# GardenSense_RevB.net
KiCad netlist of a schematic drawn in Altium Designer
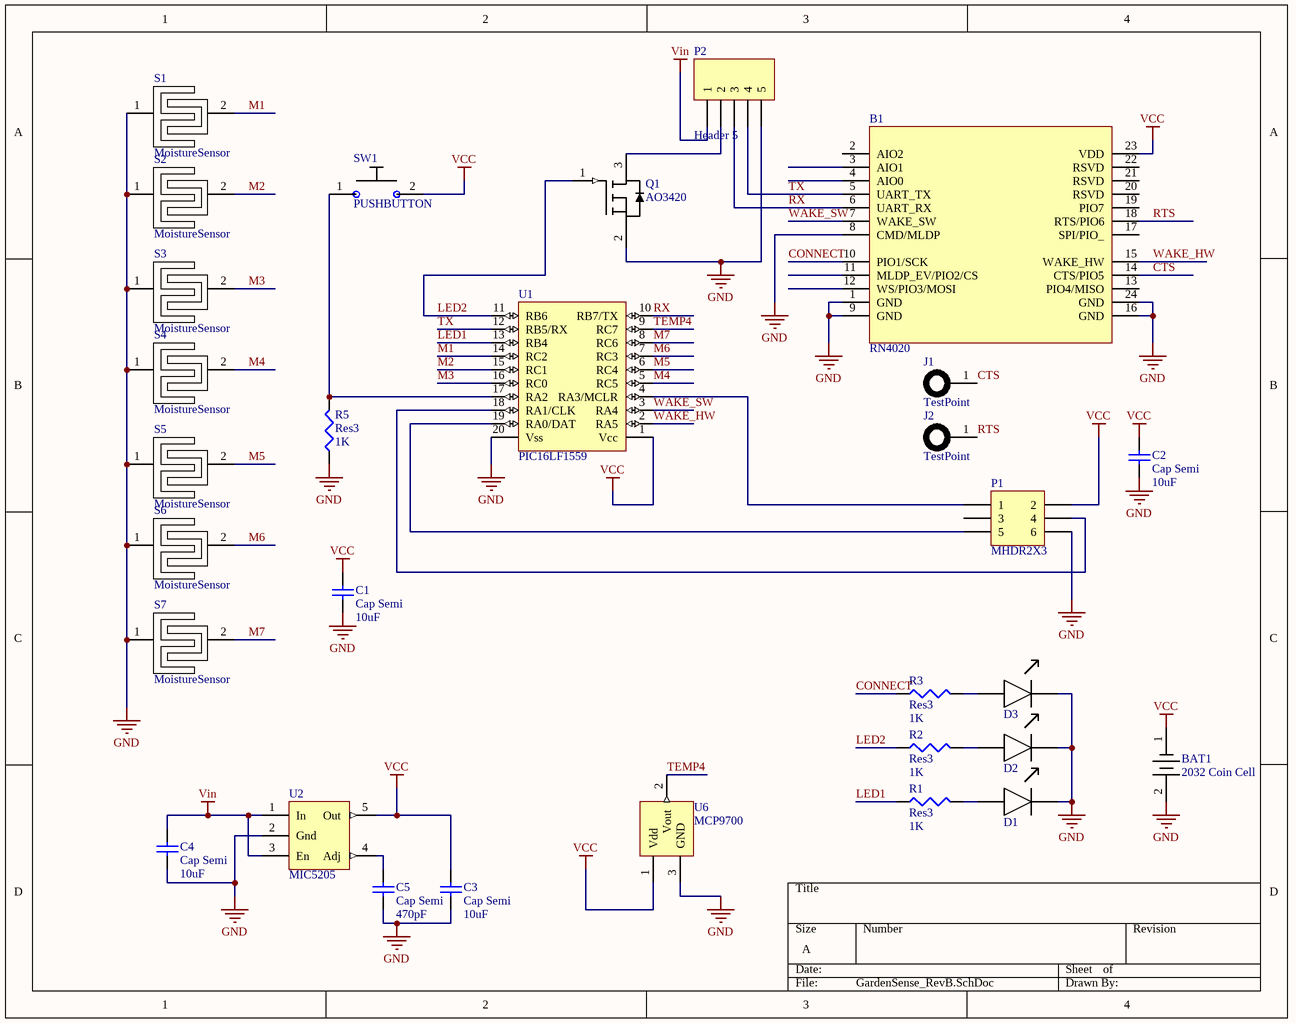
[diagram p0: GardenSense_RevB.SchDoc]

(export (version "E")
  (design (tool "Eeschema 10.0.6"))
  (components
    (comp (ref "B1") (value "RN4020") (footprint "RN4020 MODULE-24") (libsource (lib "Phil") (part "RN4020")))
    (comp (ref "BAT1")
      (value "2032 Coin Cell")
      (footprint "Keystone_3002_2032_CoinCell")
      (libsource (lib "Phil") (part "2032 Coin Cell"))
    )
    (comp (ref "C1")
      (value "Cap Semi")
      (footprint "1608[0603]")
      (description "Capacitor (Semiconductor SIM Model)")
      (fields (field (name "ALTIUM_VALUE") "10uF") (field (name "PUBLISHER") "Altium Limited"))
      (libsource (lib "Miscellaneous Devices") (part "Cap Semi"))
    )
    (comp (ref "C2")
      (value "Cap Semi")
      (footprint "1608[0603]")
      (description "Capacitor (Semiconductor SIM Model)")
      (fields (field (name "ALTIUM_VALUE") "10uF") (field (name "PUBLISHER") "Altium Limited"))
      (libsource (lib "Miscellaneous Devices") (part "Cap Semi"))
    )
    (comp (ref "C3")
      (value "Cap Semi")
      (footprint "1608[0603]")
      (description "Capacitor (Semiconductor SIM Model)")
      (fields (field (name "ALTIUM_VALUE") "10uF") (field (name "PUBLISHER") "Altium Limited"))
      (libsource (lib "Miscellaneous Devices") (part "Cap Semi"))
    )
    (comp (ref "C4")
      (value "Cap Semi")
      (footprint "1608[0603]")
      (description "Capacitor (Semiconductor SIM Model)")
      (fields (field (name "ALTIUM_VALUE") "10uF") (field (name "PUBLISHER") "Altium Limited"))
      (libsource (lib "Miscellaneous Devices") (part "Cap Semi"))
    )
    (comp (ref "C5")
      (value "Cap Semi")
      (footprint "1608[0603]")
      (description "Capacitor (Semiconductor SIM Model)")
      (fields (field (name "ALTIUM_VALUE") "470pF") (field (name "PUBLISHER") "Altium Limited"))
      (libsource (lib "Miscellaneous Devices") (part "Cap Semi"))
    )
    (comp (ref "D1") (value "LED") (footprint "603_") (libsource (lib "Phil") (part "LED")))
    (comp (ref "D2") (value "LED") (footprint "603_") (libsource (lib "Phil") (part "LED")))
    (comp (ref "D3") (value "LED") (footprint "603_") (libsource (lib "Phil") (part "LED")))
    (comp (ref "J1") (value "TestPoint") (footprint "TestPoint") (libsource (lib "Phil") (part "TestPoint")))
    (comp (ref "J2") (value "TestPoint") (footprint "TestPoint") (libsource (lib "Phil") (part "TestPoint")))
    (comp (ref "P1")
      (value "MHDR2X3")
      (footprint "MHDR2X3")
      (description "Header, 3-Pin, Dual row")
      (fields (field (name "PUBLISHER") "Altium Limited"))
      (libsource (lib "Miscellaneous Connectors") (part "MHDR2X3"))
    )
    (comp (ref "P2")
      (value "Header 5")
      (footprint "HDR1X5")
      (description "Header, 5-Pin")
      (fields (field (name "PUBLISHER") "Altium Limited"))
      (libsource (lib "Miscellaneous Connectors") (part "Header 5"))
    )
    (comp (ref "Q1") (value "AO3420") (footprint "PcbLib1:SOT23_N") (libsource (lib "Phil") (part "AO3420")))
    (comp (ref "R1")
      (value "Res3")
      (footprint "J1-0603")
      (description "Resistor")
      (fields (field (name "ALTIUM_VALUE") "1K") (field (name "PUBLISHER") "Altium Limited"))
      (libsource (lib "Miscellaneous Devices") (part "Res3"))
    )
    (comp (ref "R2")
      (value "Res3")
      (footprint "J1-0603")
      (description "Resistor")
      (fields (field (name "ALTIUM_VALUE") "1K") (field (name "PUBLISHER") "Altium Limited"))
      (libsource (lib "Miscellaneous Devices") (part "Res3"))
    )
    (comp (ref "R3")
      (value "Res3")
      (footprint "J1-0603")
      (description "Resistor")
      (fields (field (name "ALTIUM_VALUE") "1K") (field (name "PUBLISHER") "Altium Limited"))
      (libsource (lib "Miscellaneous Devices") (part "Res3"))
    )
    (comp (ref "R5")
      (value "Res3")
      (footprint "J1-0603")
      (description "Resistor")
      (fields (field (name "ALTIUM_VALUE") "1K") (field (name "PUBLISHER") "Altium Limited"))
      (libsource (lib "Miscellaneous Devices") (part "Res3"))
    )
    (comp (ref "S1")
      (value "MoistureSensor")
      (footprint "MOISTURE_2")
      (libsource (lib "Phil") (part "MoistureSensor"))
    )
    (comp (ref "S2")
      (value "MoistureSensor")
      (footprint "MOISTURE_2")
      (libsource (lib "Phil") (part "MoistureSensor"))
    )
    (comp (ref "S3")
      (value "MoistureSensor")
      (footprint "Phil:MOISTURE_2")
      (libsource (lib "Phil") (part "MoistureSensor"))
    )
    (comp (ref "S4")
      (value "MoistureSensor")
      (footprint "MOISTURE_2")
      (libsource (lib "Phil") (part "MoistureSensor"))
    )
    (comp (ref "S5")
      (value "MoistureSensor")
      (footprint "MOISTURE_2")
      (libsource (lib "Phil") (part "MoistureSensor"))
    )
    (comp (ref "S6")
      (value "MoistureSensor")
      (footprint "MOISTURE_2")
      (libsource (lib "Phil") (part "MoistureSensor"))
    )
    (comp (ref "S7")
      (value "MoistureSensor")
      (footprint "MOISTURE_2")
      (libsource (lib "Phil") (part "MoistureSensor"))
    )
    (comp (ref "SW1")
      (value "PUSHBUTTON")
      (footprint "PUSHBUTTON")
      (description "TE 5-1437565-0")
      (libsource (lib "Phil") (part "PUSHBUTTON"))
    )
    (comp (ref "U1")
      (value "PIC16LF1559")
      (footprint "SSOP-20")
      (libsource (lib "Phil") (part "PIC16LF1559"))
    )
    (comp (ref "U2")
      (value "MIC5205")
      (footprint "PcbLib1:SOT23-5_N")
      (libsource (lib "Phil") (part "MIC5205"))
    )
    (comp (ref "U6")
      (value "MCP9700")
      (footprint "Miscellaneous Devices:SOT23_M")
      (libsource (lib "Phil") (part "MCP9700"))
    )
  )
  (nets
    (net (code "1") (name "/CONNECT") (class "Default")
      (node (ref "B1") (pin "10") (pinfunction "PIO1/SCK_10") (pintype "passive"))
      (node (ref "R3") (pin "1") (pinfunction "1_1") (pintype "passive"))
    )
    (net (code "2") (name "/CTS") (class "Default")
      (node (ref "B1") (pin "14") (pinfunction "CTS/PIO5_14") (pintype "passive"))
      (node (ref "J1") (pin "1") (pinfunction "1_1") (pintype "passive"))
    )
    (net (code "3") (name "/LED1") (class "Default")
      (node (ref "R1") (pin "1") (pinfunction "1_1") (pintype "passive"))
      (node (ref "U1") (pin "13") (pinfunction "RB4_13") (pintype "bidirectional"))
    )
    (net (code "4") (name "/LED2") (class "Default")
      (node (ref "Q1") (pin "1") (pinfunction "G_1") (pintype "input"))
      (node (ref "R2") (pin "1") (pinfunction "1_1") (pintype "passive"))
      (node (ref "U1") (pin "11") (pinfunction "RB6_11") (pintype "bidirectional"))
    )
    (net (code "5") (name "/M1") (class "Default")
      (node (ref "S1") (pin "2") (pinfunction "2_2") (pintype "passive"))
      (node (ref "U1") (pin "14") (pinfunction "RC2_14") (pintype "bidirectional"))
    )
    (net (code "6") (name "/M2") (class "Default")
      (node (ref "S2") (pin "2") (pinfunction "2_2") (pintype "passive"))
      (node (ref "U1") (pin "15") (pinfunction "RC1_15") (pintype "bidirectional"))
    )
    (net (code "7") (name "/M3") (class "Default")
      (node (ref "S3") (pin "2") (pinfunction "2_2") (pintype "passive"))
      (node (ref "U1") (pin "16") (pinfunction "RC0_16") (pintype "bidirectional"))
    )
    (net (code "8") (name "/M4") (class "Default")
      (node (ref "S4") (pin "2") (pinfunction "2_2") (pintype "passive"))
      (node (ref "U1") (pin "5") (pinfunction "RC5_5") (pintype "bidirectional"))
    )
    (net (code "9") (name "/M5") (class "Default")
      (node (ref "S5") (pin "2") (pinfunction "2_2") (pintype "passive"))
      (node (ref "U1") (pin "6") (pinfunction "RC4_6") (pintype "bidirectional"))
    )
    (net (code "10") (name "/M6") (class "Default")
      (node (ref "S6") (pin "2") (pinfunction "2_2") (pintype "passive"))
      (node (ref "U1") (pin "7") (pinfunction "RC3_7") (pintype "bidirectional"))
    )
    (net (code "11") (name "/M7") (class "Default")
      (node (ref "S7") (pin "2") (pinfunction "2_2") (pintype "passive"))
      (node (ref "U1") (pin "8") (pinfunction "RC6_8") (pintype "bidirectional"))
    )
    (net (code "12") (name "/RTS") (class "Default")
      (node (ref "B1") (pin "18") (pinfunction "RTS/PIO6_18") (pintype "passive"))
      (node (ref "J2") (pin "1") (pinfunction "1_1") (pintype "passive"))
    )
    (net (code "13") (name "/RX") (class "Default")
      (node (ref "B1") (pin "6") (pinfunction "UART_RX_6") (pintype "passive"))
      (node (ref "P2") (pin "3") (pinfunction "3_3") (pintype "passive"))
      (node (ref "U1") (pin "10") (pinfunction "RB7/TX_10") (pintype "bidirectional"))
    )
    (net (code "14") (name "/TEMP4") (class "Default")
      (node (ref "U1") (pin "9") (pinfunction "RC7_9") (pintype "bidirectional"))
      (node (ref "U6") (pin "2") (pinfunction "Vout_2") (pintype "output"))
    )
    (net (code "15") (name "/TX") (class "Default")
      (node (ref "B1") (pin "5") (pinfunction "UART_TX_5") (pintype "passive"))
      (node (ref "P2") (pin "4") (pinfunction "4_4") (pintype "passive"))
      (node (ref "U1") (pin "12") (pinfunction "RB5/RX_12") (pintype "bidirectional"))
    )
    (net (code "16") (name "/WAKE_HW") (class "Default")
      (node (ref "B1") (pin "15") (pinfunction "WAKE_HW_15") (pintype "passive"))
      (node (ref "U1") (pin "2") (pinfunction "RA5_2") (pintype "bidirectional"))
    )
    (net (code "17") (name "/WAKE_SW") (class "Default")
      (node (ref "B1") (pin "7") (pinfunction "WAKE_SW_7") (pintype "passive"))
      (node (ref "U1") (pin "3") (pinfunction "RA4_3") (pintype "bidirectional"))
    )
    (net (code "18") (name "GND") (class "Default")
      (node (ref "B1") (pin "1") (pinfunction "GND_1") (pintype "power_in"))
      (node (ref "B1") (pin "16") (pinfunction "GND_16") (pintype "power_in"))
      (node (ref "B1") (pin "24") (pinfunction "GND_24") (pintype "passive"))
      (node (ref "B1") (pin "8") (pinfunction "CMD/MLDP_8") (pintype "passive"))
      (node (ref "B1") (pin "9") (pinfunction "GND_9") (pintype "power_in"))
      (node (ref "BAT1") (pin "2") (pinfunction "2_2") (pintype "passive"))
      (node (ref "C1") (pin "1") (pinfunction "1_1") (pintype "passive"))
      (node (ref "C2") (pin "1") (pinfunction "1_1") (pintype "passive"))
      (node (ref "C3") (pin "1") (pinfunction "1_1") (pintype "passive"))
      (node (ref "C4") (pin "1") (pinfunction "1_1") (pintype "passive"))
      (node (ref "C5") (pin "1") (pinfunction "1_1") (pintype "passive"))
      (node (ref "D1") (pin "2") (pinfunction "2_2") (pintype "passive"))
      (node (ref "D2") (pin "2") (pinfunction "2_2") (pintype "passive"))
      (node (ref "D3") (pin "2") (pinfunction "2_2") (pintype "passive"))
      (node (ref "P1") (pin "6") (pinfunction "6_6") (pintype "passive"))
      (node (ref "P2") (pin "5") (pinfunction "5_5") (pintype "passive"))
      (node (ref "Q1") (pin "2") (pinfunction "S_2") (pintype "power_in"))
      (node (ref "R5") (pin "1") (pinfunction "1_1") (pintype "passive"))
      (node (ref "S1") (pin "1") (pinfunction "1_1") (pintype "passive"))
      (node (ref "S2") (pin "1") (pinfunction "1_1") (pintype "passive"))
      (node (ref "S3") (pin "1") (pinfunction "1_1") (pintype "passive"))
      (node (ref "S4") (pin "1") (pinfunction "1_1") (pintype "passive"))
      (node (ref "S5") (pin "1") (pinfunction "1_1") (pintype "passive"))
      (node (ref "S6") (pin "1") (pinfunction "1_1") (pintype "passive"))
      (node (ref "S7") (pin "1") (pinfunction "1_1") (pintype "passive"))
      (node (ref "U1") (pin "20") (pinfunction "Vss_20") (pintype "power_in"))
      (node (ref "U2") (pin "2") (pinfunction "Gnd_2") (pintype "power_in"))
      (node (ref "U6") (pin "3") (pinfunction "GND_3") (pintype "power_in"))
    )
    (net (code "19") (name "Net-(D1-Pad1)") (class "Default")
      (node (ref "D1") (pin "1") (pinfunction "1_1") (pintype "passive"))
      (node (ref "R1") (pin "2") (pinfunction "2_2") (pintype "passive"))
    )
    (net (code "20") (name "Net-(D2-Pad1)") (class "Default")
      (node (ref "D2") (pin "1") (pinfunction "1_1") (pintype "passive"))
      (node (ref "R2") (pin "2") (pinfunction "2_2") (pintype "passive"))
    )
    (net (code "21") (name "Net-(D3-Pad1)") (class "Default")
      (node (ref "D3") (pin "1") (pinfunction "1_1") (pintype "passive"))
      (node (ref "R3") (pin "2") (pinfunction "2_2") (pintype "passive"))
    )
    (net (code "22") (name "Net-(Q1-D)") (class "Default")
      (node (ref "P2") (pin "2") (pinfunction "2_2") (pintype "passive"))
      (node (ref "Q1") (pin "3") (pinfunction "D_3") (pintype "power_in"))
    )
    (net (code "23") (name "Net-(U1-RA0{slash}DAT)") (class "Default")
      (node (ref "P1") (pin "5") (pinfunction "5_5") (pintype "passive"))
      (node (ref "U1") (pin "19") (pinfunction "RA0/DAT_19") (pintype "bidirectional"))
    )
    (net (code "24") (name "Net-(U1-RA1{slash}CLK)") (class "Default")
      (node (ref "P1") (pin "4") (pinfunction "4_4") (pintype "passive"))
      (node (ref "U1") (pin "18") (pinfunction "RA1/CLK_18") (pintype "bidirectional"))
    )
    (net (code "25") (name "Net-(U1-RA2)") (class "Default")
      (node (ref "R5") (pin "2") (pinfunction "2_2") (pintype "passive"))
      (node (ref "SW1") (pin "1") (pinfunction "1_1") (pintype "passive"))
      (node (ref "U1") (pin "17") (pinfunction "RA2_17") (pintype "bidirectional"))
    )
    (net (code "26") (name "Net-(U1-RA3{slash}MCLR)") (class "Default")
      (node (ref "P1") (pin "1") (pinfunction "1_1") (pintype "passive"))
      (node (ref "U1") (pin "4") (pinfunction "RA3/MCLR_4") (pintype "bidirectional"))
    )
    (net (code "27") (name "Net-(U2-Adj)") (class "Default")
      (node (ref "C5") (pin "2") (pinfunction "2_2") (pintype "passive"))
      (node (ref "U2") (pin "4") (pinfunction "Adj_4") (pintype "output"))
    )
    (net (code "28") (name "VCC") (class "Default")
      (node (ref "B1") (pin "23") (pinfunction "VDD_23") (pintype "power_in"))
      (node (ref "BAT1") (pin "1") (pinfunction "1_1") (pintype "passive"))
      (node (ref "C1") (pin "2") (pinfunction "2_2") (pintype "passive"))
      (node (ref "C2") (pin "2") (pinfunction "2_2") (pintype "passive"))
      (node (ref "C3") (pin "2") (pinfunction "2_2") (pintype "passive"))
      (node (ref "P1") (pin "2") (pinfunction "2_2") (pintype "passive"))
      (node (ref "SW1") (pin "2") (pinfunction "2_2") (pintype "passive"))
      (node (ref "U1") (pin "1") (pinfunction "Vcc_1") (pintype "power_in"))
      (node (ref "U2") (pin "5") (pinfunction "Out_5") (pintype "output"))
      (node (ref "U6") (pin "1") (pinfunction "Vdd_1") (pintype "power_in"))
    )
    (net (code "29") (name "Vin") (class "Default")
      (node (ref "C4") (pin "2") (pinfunction "2_2") (pintype "passive"))
      (node (ref "P2") (pin "1") (pinfunction "1_1") (pintype "passive"))
      (node (ref "U2") (pin "1") (pinfunction "In_1") (pintype "power_in"))
      (node (ref "U2") (pin "3") (pinfunction "En_3") (pintype "power_in"))
    )
    (net (code "30") (name "unconnected-(B1-AIO0-Pad4)") (class "Default")
      (node (ref "B1") (pin "4") (pinfunction "AIO0_4") (pintype "passive"))
    )
    (net (code "31") (name "unconnected-(B1-AIO1-Pad3)") (class "Default")
      (node (ref "B1") (pin "3") (pinfunction "AIO1_3") (pintype "passive"))
    )
    (net (code "32") (name "unconnected-(B1-AIO2-Pad2)") (class "Default")
      (node (ref "B1") (pin "2") (pinfunction "AIO2_2") (pintype "passive"))
    )
    (net (code "33") (name "unconnected-(B1-MLDP_EV{slash}PIO2{slash}CS-Pad11)") (class "Default")
      (node (ref "B1") (pin "11") (pinfunction "MLDP_EV/PIO2/CS_11") (pintype "passive"))
    )
    (net (code "34") (name "unconnected-(B1-PIO4{slash}MISO-Pad13)") (class "Default")
      (node (ref "B1") (pin "13") (pinfunction "PIO4/MISO_13") (pintype "passive"))
    )
    (net (code "35") (name "unconnected-(B1-PIO7-Pad19)") (class "Default")
      (node (ref "B1") (pin "19") (pinfunction "PIO7_19") (pintype "passive"))
    )
    (net (code "36") (name "unconnected-(B1-RSVD-Pad20)") (class "Default")
      (node (ref "B1") (pin "20") (pinfunction "RSVD_20") (pintype "passive"))
    )
    (net (code "37") (name "unconnected-(B1-RSVD-Pad21)") (class "Default")
      (node (ref "B1") (pin "21") (pinfunction "RSVD_21") (pintype "passive"))
    )
    (net (code "38") (name "unconnected-(B1-RSVD-Pad22)") (class "Default")
      (node (ref "B1") (pin "22") (pinfunction "RSVD_22") (pintype "passive"))
    )
    (net (code "39") (name "unconnected-(B1-SPI{slash}PIO_-Pad17)") (class "Default")
      (node (ref "B1") (pin "17") (pinfunction "SPI/PIO__17") (pintype "passive"))
    )
    (net (code "40") (name "unconnected-(B1-WS{slash}PIO3{slash}MOSI-Pad12)") (class "Default")
      (node (ref "B1") (pin "12") (pinfunction "WS/PIO3/MOSI_12") (pintype "passive"))
    )
    (net (code "41") (name "unconnected-(P1-Pad3)") (class "Default")
      (node (ref "P1") (pin "3") (pinfunction "3_3") (pintype "passive"))
    )
  )
)
